# ecternal_i2c.net
KiCad netlist of a schematic drawn in Altium Designer
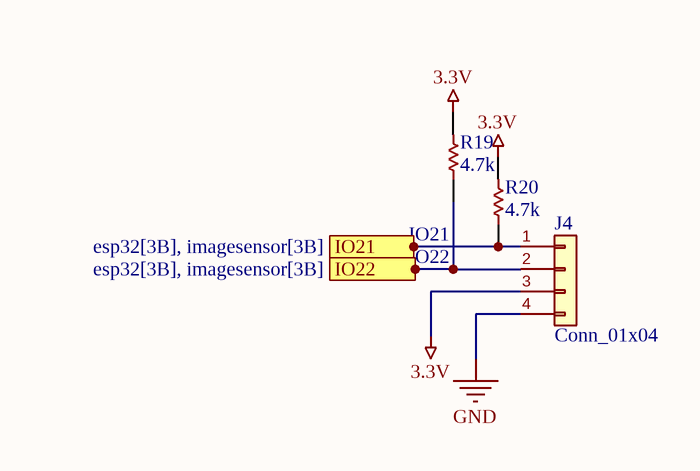
[diagram p0: ecternal_i2c.SchDoc]

(export (version "E")
  (design (tool "Eeschema 10.0.6"))
  (components
    (comp (ref "J4")
      (value "Conn_01x04")
      (footprint "connector 4pin")
      (libsource (lib "Thermal_Camera") (part "Conn_01x04"))
    )
    (comp (ref "R19")
      (value "4.7k")
      (footprint "RESC2013X70X40NL20T20")
      (description "Chip Resistor, 1 KOhm, +/- 1%, 125 mW, -55 to 155 degC, 0805 (2012 Metric), RoHS, Tape and Reel")
      (fields (field (name "TOLERANCE") "1%") (field (name "MANUFACTURER") "Yageo"))
      (libsource (lib "Thermal_Camera") (part "CMP-2100-03671-1"))
    )
    (comp (ref "R20")
      (value "4.7k")
      (footprint "RESC2013X70X40NL20T20")
      (description "Chip Resistor, 1 KOhm, +/- 1%, 125 mW, -55 to 155 degC, 0805 (2012 Metric), RoHS, Tape and Reel")
      (fields (field (name "TOLERANCE") "1%") (field (name "MANUFACTURER") "Yageo"))
      (libsource (lib "Thermal_Camera") (part "CMP-2100-03671-1"))
    )
  )
  (nets
    (net (code "1") (name "/IO21") (class "Default")
      (node (ref "J4") (pin "1") (pinfunction "Pin_1_1") (pintype "passive"))
      (node (ref "R20") (pin "1") (pinfunction "1_1") (pintype "passive"))
    )
    (net (code "2") (name "/IO22") (class "Default")
      (node (ref "J4") (pin "2") (pinfunction "Pin_2_2") (pintype "passive"))
      (node (ref "R19") (pin "1") (pinfunction "1_1") (pintype "passive"))
    )
    (net (code "3") (name "3.3V") (class "Default")
      (node (ref "J4") (pin "3") (pinfunction "Pin_3_3") (pintype "passive"))
      (node (ref "R19") (pin "2") (pinfunction "2_2") (pintype "passive"))
      (node (ref "R20") (pin "2") (pinfunction "2_2") (pintype "passive"))
    )
    (net (code "4") (name "GND") (class "Default")
      (node (ref "J4") (pin "4") (pinfunction "Pin_4_4") (pintype "passive"))
    )
  )
)
